# AuxHalfH.net
KiCad netlist of a schematic drawn in Altium Designer
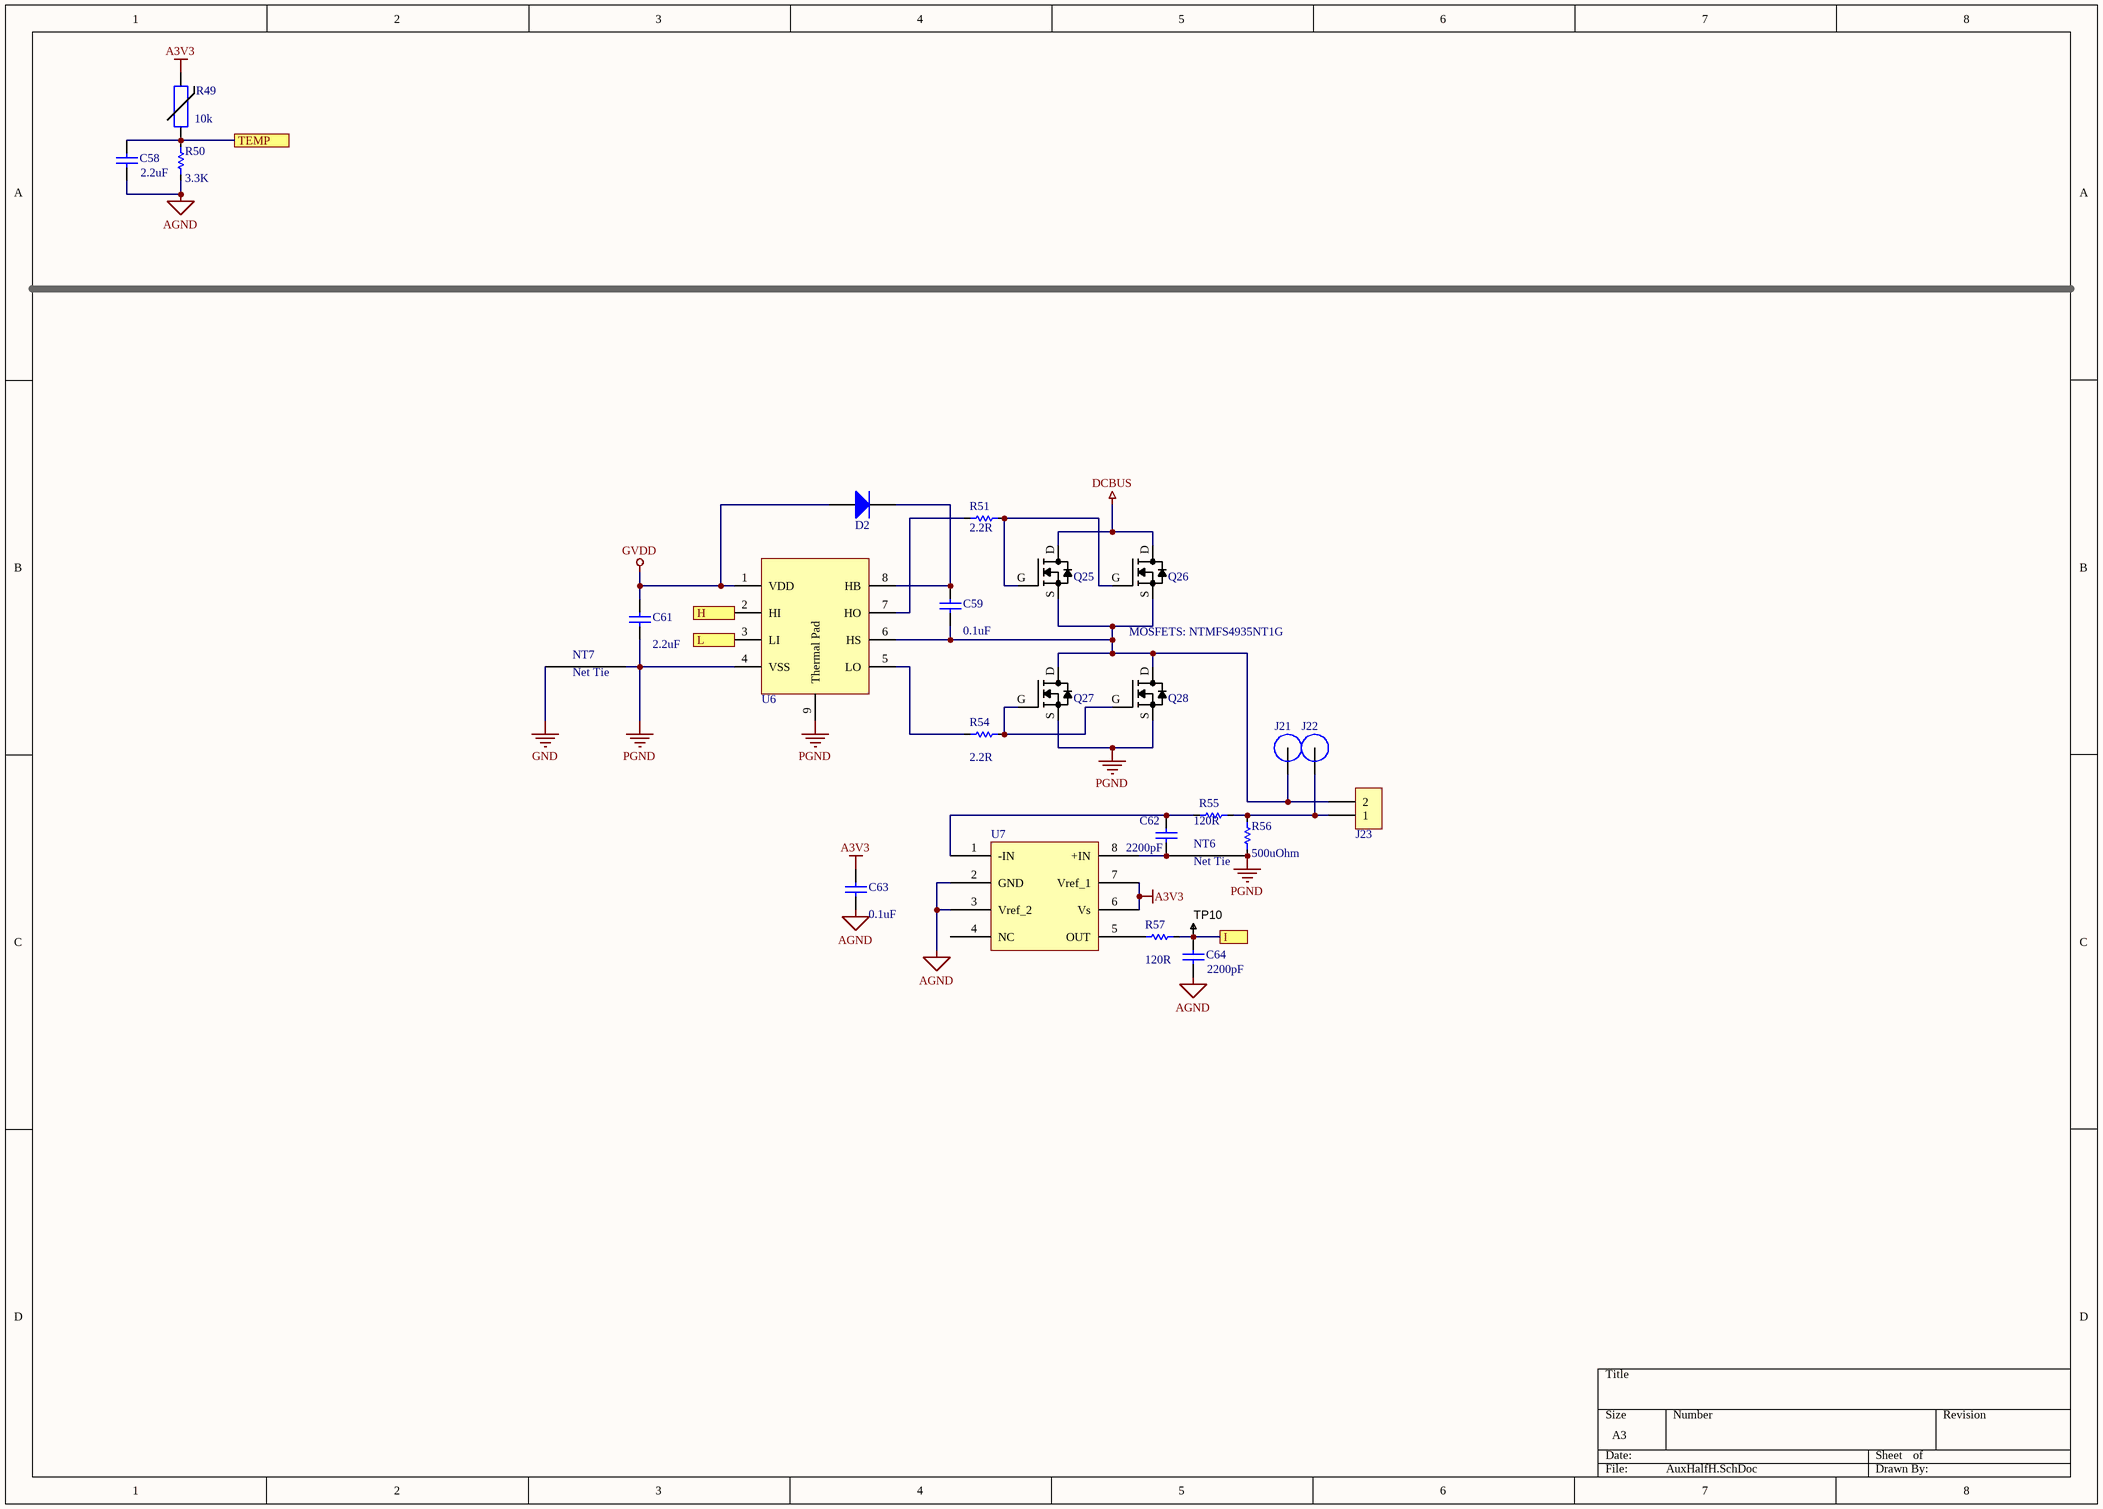
[diagram p0: AuxHalfH.SchDoc]

(export (version "E")
  (design (tool "Eeschema 10.0.6"))
  (components
    (comp (ref "C58")
      (value "2.2uF")
      (footprint "C0603")
      (description "CAP CER 2.2UF 16V X5R 0603")
      (fields (field (name "Comment") "Cap") (field (name "PUBLISHER") "Altium Limited"))
      (libsource (lib "Component footprints") (part "Cap"))
    )
    (comp (ref "C59")
      (value "0.1uF")
      (footprint "C0603")
      (description "CAP CER 0.1UF 50V X7R 0603")
      (fields (field (name "Comment") "Cap") (field (name "PUBLISHER") "Altium Limited"))
      (libsource (lib "Component footprints") (part "Cap"))
    )
    (comp (ref "C61")
      (value "2.2uF")
      (footprint "C0603")
      (description "CAP CER 2.2UF 16V X5R 0603")
      (fields (field (name "Comment") "Cap") (field (name "PUBLISHER") "Altium Limited"))
      (libsource (lib "Component footprints") (part "Cap"))
    )
    (comp (ref "C62")
      (value "2200pF")
      (footprint "C0603")
      (description "CAP CER 2200PF 50V NP0 0603")
      (fields (field (name "Comment") "Cap") (field (name "PUBLISHER") "Altium Limited"))
      (libsource (lib "Component footprints") (part "Cap"))
    )
    (comp (ref "C63")
      (value "0.1uF")
      (footprint "C0603")
      (description "CAP CER 0.1UF 50V X7R 0603")
      (fields (field (name "Comment") "Cap") (field (name "PUBLISHER") "Altium Limited"))
      (libsource (lib "Component footprints") (part "Cap"))
    )
    (comp (ref "C64")
      (value "2200pF")
      (footprint "C0603")
      (description "CAP CER 2200PF 50V NP0 0603")
      (fields (field (name "Comment") "Cap") (field (name "PUBLISHER") "Altium Limited"))
      (libsource (lib "Component footprints") (part "Cap"))
    )
    (comp (ref "D2")
      (value "~")
      (footprint "DIOM2717X10N")
      (description "Rectifier Diode, Single, 40 V, 1 A, SOD-123FL, 2, 550 mV")
      (libsource (lib "CustomComponents") (part "MBR140SFT1G"))
    )
    (comp (ref "J21")
      (value "~")
      (footprint "M3 Spade Hole")
      (description "M3 Spade Terminal")
      (libsource (lib "CustomComponents") (part "M3 Spade Terminal"))
    )
    (comp (ref "J22")
      (value "~")
      (footprint "M3 Spade Hole")
      (description "M3 Spade Terminal")
      (libsource (lib "CustomComponents") (part "M3 Spade Terminal"))
    )
    (comp (ref "J23")
      (value "1868076")
      (footprint "1868076")
      (description "CONN TERM BLOCK 2POS 7.62MM")
      (fields (field (name "MANUFACTURER") "Phoenix Contact") (field (name "VOLTAGE") "300V"))
      (libsource (lib "CustomComponents") (part "1868076"))
    )
    (comp (ref "NT6")
      (value "0.25mm")
      (footprint "NetTie_0.25mm")
      (libsource (lib "CustomComponents") (part "NetTie_0.25mm"))
    )
    (comp (ref "NT7")
      (value "0.25mm")
      (footprint "NetTie_0.25mm")
      (libsource (lib "CustomComponents") (part "NetTie_0.25mm"))
    )
    (comp (ref "Q25")
      (value "FILL_FOOTPRINT")
      (footprint "SO8FL_FILL")
      (description "MOSFET N-CH 30V 13A SO8FL")
      (fields
        (field (name "MANUFACTURER") "ON Semiconductor")
        (field (name "MANUFACTURER PART NUMBER") "NTMFS4935NT1G")
      )
      (libsource (lib "CustomComponents") (part "NTMFS4935NT1G"))
    )
    (comp (ref "Q26")
      (value "~")
      (footprint "SO8FL")
      (description "MOSFET N-CH 30V 13A SO8FL")
      (fields
        (field (name "MANUFACTURER") "ON Semiconductor")
        (field (name "MANUFACTURER PART NUMBER") "NTMFS4935NT1G")
      )
      (libsource (lib "CustomComponents") (part "NTMFS4935NT1G"))
    )
    (comp (ref "Q27")
      (value "~")
      (footprint "SO8FL")
      (description "MOSFET N-CH 30V 13A SO8FL")
      (fields
        (field (name "MANUFACTURER") "ON Semiconductor")
        (field (name "MANUFACTURER PART NUMBER") "NTMFS4935NT1G")
      )
      (libsource (lib "CustomComponents") (part "NTMFS4935NT1G"))
    )
    (comp (ref "Q28")
      (value "~")
      (footprint "SO8FL")
      (description "MOSFET N-CH 30V 13A SO8FL")
      (fields
        (field (name "MANUFACTURER") "ON Semiconductor")
        (field (name "MANUFACTURER PART NUMBER") "NTMFS4935NT1G")
      )
      (libsource (lib "CustomComponents") (part "NTMFS4935NT1G"))
    )
    (comp (ref "R49")
      (value "10k")
      (footprint "RESC1005X40N")
      (description "THERMISTOR 10K OHM NTC 0402 SMD")
      (libsource (lib "CustomComponents") (part "NCP15XH103F03RC"))
    )
    (comp (ref "R50")
      (value "3.3K")
      (footprint "R0603")
      (description "Resistor")
      (fields (field (name "Comment") "Res") (field (name "PUBLISHER") "Altium Limited"))
      (libsource (lib "Component footprints") (part "Res"))
    )
    (comp (ref "R51")
      (value "2.2R")
      (footprint "R0603")
      (description "Resistor")
      (fields (field (name "Comment") "Res") (field (name "PUBLISHER") "Altium Limited"))
      (libsource (lib "Component footprints") (part "Res"))
    )
    (comp (ref "R54")
      (value "2.2R")
      (footprint "R0603")
      (description "Resistor")
      (fields (field (name "Comment") "Res") (field (name "PUBLISHER") "Altium Limited"))
      (libsource (lib "Component footprints") (part "Res"))
    )
    (comp (ref "R55")
      (value "120R")
      (footprint "R0603")
      (description "Resistor")
      (fields (field (name "Comment") "Res") (field (name "PUBLISHER") "Altium Limited"))
      (libsource (lib "Component footprints") (part "Res"))
    )
    (comp (ref "R56")
      (value "500uOhm")
      (footprint "R2512")
      (description "RES SMD 0.0005 OHM 1% 3W 2512")
      (fields (field (name "Comment") "Res") (field (name "PUBLISHER") "Altium Limited"))
      (libsource (lib "Component footprints") (part "Res"))
    )
    (comp (ref "R57")
      (value "120R")
      (footprint "R0603")
      (description "Resistor")
      (fields (field (name "Comment") "Res") (field (name "PUBLISHER") "Altium Limited"))
      (libsource (lib "Component footprints") (part "Res"))
    )
    (comp (ref "TP10")
      (value "TESTPOINT")
      (footprint "TP-R30")
      (description "SMD test pin")
      (libsource (lib "PBL - Test Points") (part "TESTPOINT"))
    )
    (comp (ref "U6")
      (value "~")
      (footprint "SON80P400X80_HS-9N")
      (description "DRIVER, MOSFET, HALF BRIDGE, WSON-8, 1A")
      (libsource (lib "CustomComponents") (part "LM5109BSD/NOPB"))
    )
    (comp (ref "U7")
      (value "~")
      (footprint "SOIC127P600X175-8N")
      (description "ANALOG DEVICES Current Sense Amplifier, Bidirectional, 1, 130 µA, NSOIC")
      (libsource (lib "CustomComponents") (part "AD8418WBRZ"))
    )
  )
  (nets
    (net (code "1") (name "/H") (class "Default")
      (node (ref "U6") (pin "2") (pinfunction "HI_2") (pintype "passive"))
    )
    (net (code "2") (name "/I") (class "Default")
      (node (ref "C64") (pin "2") (pinfunction "2_2") (pintype "passive"))
      (node (ref "R57") (pin "2") (pinfunction "2_2") (pintype "passive"))
      (node (ref "TP10") (pin "1") (pintype "passive"))
    )
    (net (code "3") (name "/L") (class "Default")
      (node (ref "U6") (pin "3") (pinfunction "LI_3") (pintype "passive"))
    )
    (net (code "4") (name "/TEMP") (class "Default")
      (node (ref "C58") (pin "2") (pinfunction "2_2") (pintype "passive"))
      (node (ref "R49") (pin "1") (pinfunction "0_1") (pintype "passive"))
      (node (ref "R50") (pin "2") (pinfunction "2_2") (pintype "passive"))
    )
    (net (code "5") (name "A3V3") (class "Default")
      (node (ref "C63") (pin "2") (pinfunction "2_2") (pintype "passive"))
      (node (ref "R49") (pin "2") (pinfunction "0_2") (pintype "passive"))
      (node (ref "U7") (pin "6") (pinfunction "Vs_6") (pintype "passive"))
      (node (ref "U7") (pin "7") (pinfunction "Vref_1_7") (pintype "passive"))
    )
    (net (code "6") (name "AGND") (class "Default")
      (node (ref "C58") (pin "1") (pinfunction "1_1") (pintype "passive"))
      (node (ref "C63") (pin "1") (pinfunction "1_1") (pintype "passive"))
      (node (ref "C64") (pin "1") (pinfunction "1_1") (pintype "passive"))
      (node (ref "R50") (pin "1") (pinfunction "1_1") (pintype "passive"))
      (node (ref "U7") (pin "2") (pinfunction "GND_2") (pintype "passive"))
      (node (ref "U7") (pin "3") (pinfunction "Vref_2_3") (pintype "passive"))
    )
    (net (code "7") (name "DCBUS") (class "Default")
      (node (ref "Q25") (pin "D") (pinfunction "D_D") (pintype "passive"))
      (node (ref "Q26") (pin "D") (pinfunction "D_D") (pintype "passive"))
    )
    (net (code "8") (name "GND") (class "Default") (node (ref "NT7") (pin "1") (pintype "passive")))
    (net (code "9") (name "GVDD") (class "Default")
      (node (ref "C61") (pin "2") (pinfunction "2_2") (pintype "passive"))
      (node (ref "D2") (pin "A") (pinfunction "A_A") (pintype "passive"))
      (node (ref "U6") (pin "1") (pinfunction "VDD_1") (pintype "passive"))
    )
    (net (code "10") (name "Net-(J22-Pad1)") (class "Default")
      (node (ref "J22") (pin "1") (pinfunction "1_1") (pintype "passive"))
      (node (ref "J23") (pin "1") (pinfunction "1_1") (pintype "passive"))
      (node (ref "R55") (pin "1") (pinfunction "1_1") (pintype "passive"))
      (node (ref "R56") (pin "2") (pinfunction "2_2") (pintype "passive"))
    )
    (net (code "11") (name "Net-(Q25-PadG)") (class "Default")
      (node (ref "Q25") (pin "G") (pinfunction "G_G") (pintype "passive"))
      (node (ref "Q26") (pin "G") (pinfunction "G_G") (pintype "passive"))
      (node (ref "R51") (pin "1") (pinfunction "1_1") (pintype "passive"))
    )
    (net (code "12") (name "Net-(Q27-PadG)") (class "Default")
      (node (ref "Q27") (pin "G") (pinfunction "G_G") (pintype "passive"))
      (node (ref "Q28") (pin "G") (pinfunction "G_G") (pintype "passive"))
      (node (ref "R54") (pin "1") (pinfunction "1_1") (pintype "passive"))
    )
    (net (code "13") (name "Net-(U6-HB)") (class "Default")
      (node (ref "C59") (pin "2") (pinfunction "2_2") (pintype "passive"))
      (node (ref "D2") (pin "K") (pinfunction "K_K") (pintype "passive"))
      (node (ref "U6") (pin "8") (pinfunction "HB_8") (pintype "passive"))
    )
    (net (code "14") (name "Net-(U6-HO)") (class "Default")
      (node (ref "R51") (pin "2") (pinfunction "2_2") (pintype "passive"))
      (node (ref "U6") (pin "7") (pinfunction "HO_7") (pintype "passive"))
    )
    (net (code "15") (name "Net-(U6-HS)") (class "Default")
      (node (ref "C59") (pin "1") (pinfunction "1_1") (pintype "passive"))
      (node (ref "J21") (pin "1") (pinfunction "1_1") (pintype "passive"))
      (node (ref "J23") (pin "2") (pinfunction "2_2") (pintype "passive"))
      (node (ref "Q25") (pin "S") (pinfunction "S_S") (pintype "passive"))
      (node (ref "Q26") (pin "S") (pinfunction "S_S") (pintype "passive"))
      (node (ref "Q27") (pin "D") (pinfunction "D_D") (pintype "passive"))
      (node (ref "Q28") (pin "D") (pinfunction "D_D") (pintype "passive"))
      (node (ref "U6") (pin "6") (pinfunction "HS_6") (pintype "passive"))
    )
    (net (code "16") (name "Net-(U6-LO)") (class "Default")
      (node (ref "R54") (pin "2") (pinfunction "2_2") (pintype "passive"))
      (node (ref "U6") (pin "5") (pinfunction "LO_5") (pintype "passive"))
    )
    (net (code "17") (name "Net-(U7-+IN)") (class "Default")
      (node (ref "C62") (pin "1") (pinfunction "1_1") (pintype "passive"))
      (node (ref "NT6") (pin "1") (pintype "passive"))
      (node (ref "U7") (pin "8") (pinfunction "+IN_8") (pintype "passive"))
    )
    (net (code "18") (name "Net-(U7--IN)") (class "Default")
      (node (ref "C62") (pin "2") (pinfunction "2_2") (pintype "passive"))
      (node (ref "R55") (pin "2") (pinfunction "2_2") (pintype "passive"))
      (node (ref "U7") (pin "1") (pinfunction "-IN_1") (pintype "passive"))
    )
    (net (code "19") (name "Net-(U7-OUT)") (class "Default")
      (node (ref "R57") (pin "1") (pinfunction "1_1") (pintype "passive"))
      (node (ref "U7") (pin "5") (pinfunction "OUT_5") (pintype "passive"))
    )
    (net (code "20") (name "PGND") (class "Default")
      (node (ref "C61") (pin "1") (pinfunction "1_1") (pintype "passive"))
      (node (ref "NT6") (pin "2") (pintype "passive"))
      (node (ref "NT7") (pin "2") (pintype "passive"))
      (node (ref "Q27") (pin "S") (pinfunction "S_S") (pintype "passive"))
      (node (ref "Q28") (pin "S") (pinfunction "S_S") (pintype "passive"))
      (node (ref "R56") (pin "1") (pinfunction "1_1") (pintype "passive"))
      (node (ref "U6") (pin "4") (pinfunction "VSS_4") (pintype "passive"))
      (node (ref "U6") (pin "9") (pinfunction "Thermal_Pad_9") (pintype "passive"))
    )
    (net (code "21") (name "unconnected-(U7-NC-Pad4)") (class "Default")
      (node (ref "U7") (pin "4") (pinfunction "NC_4") (pintype "passive"))
    )
  )
)
